# OSO-SWAT-A1-05-BLUE.net
KiCad netlist of a schematic drawn in EAGLE
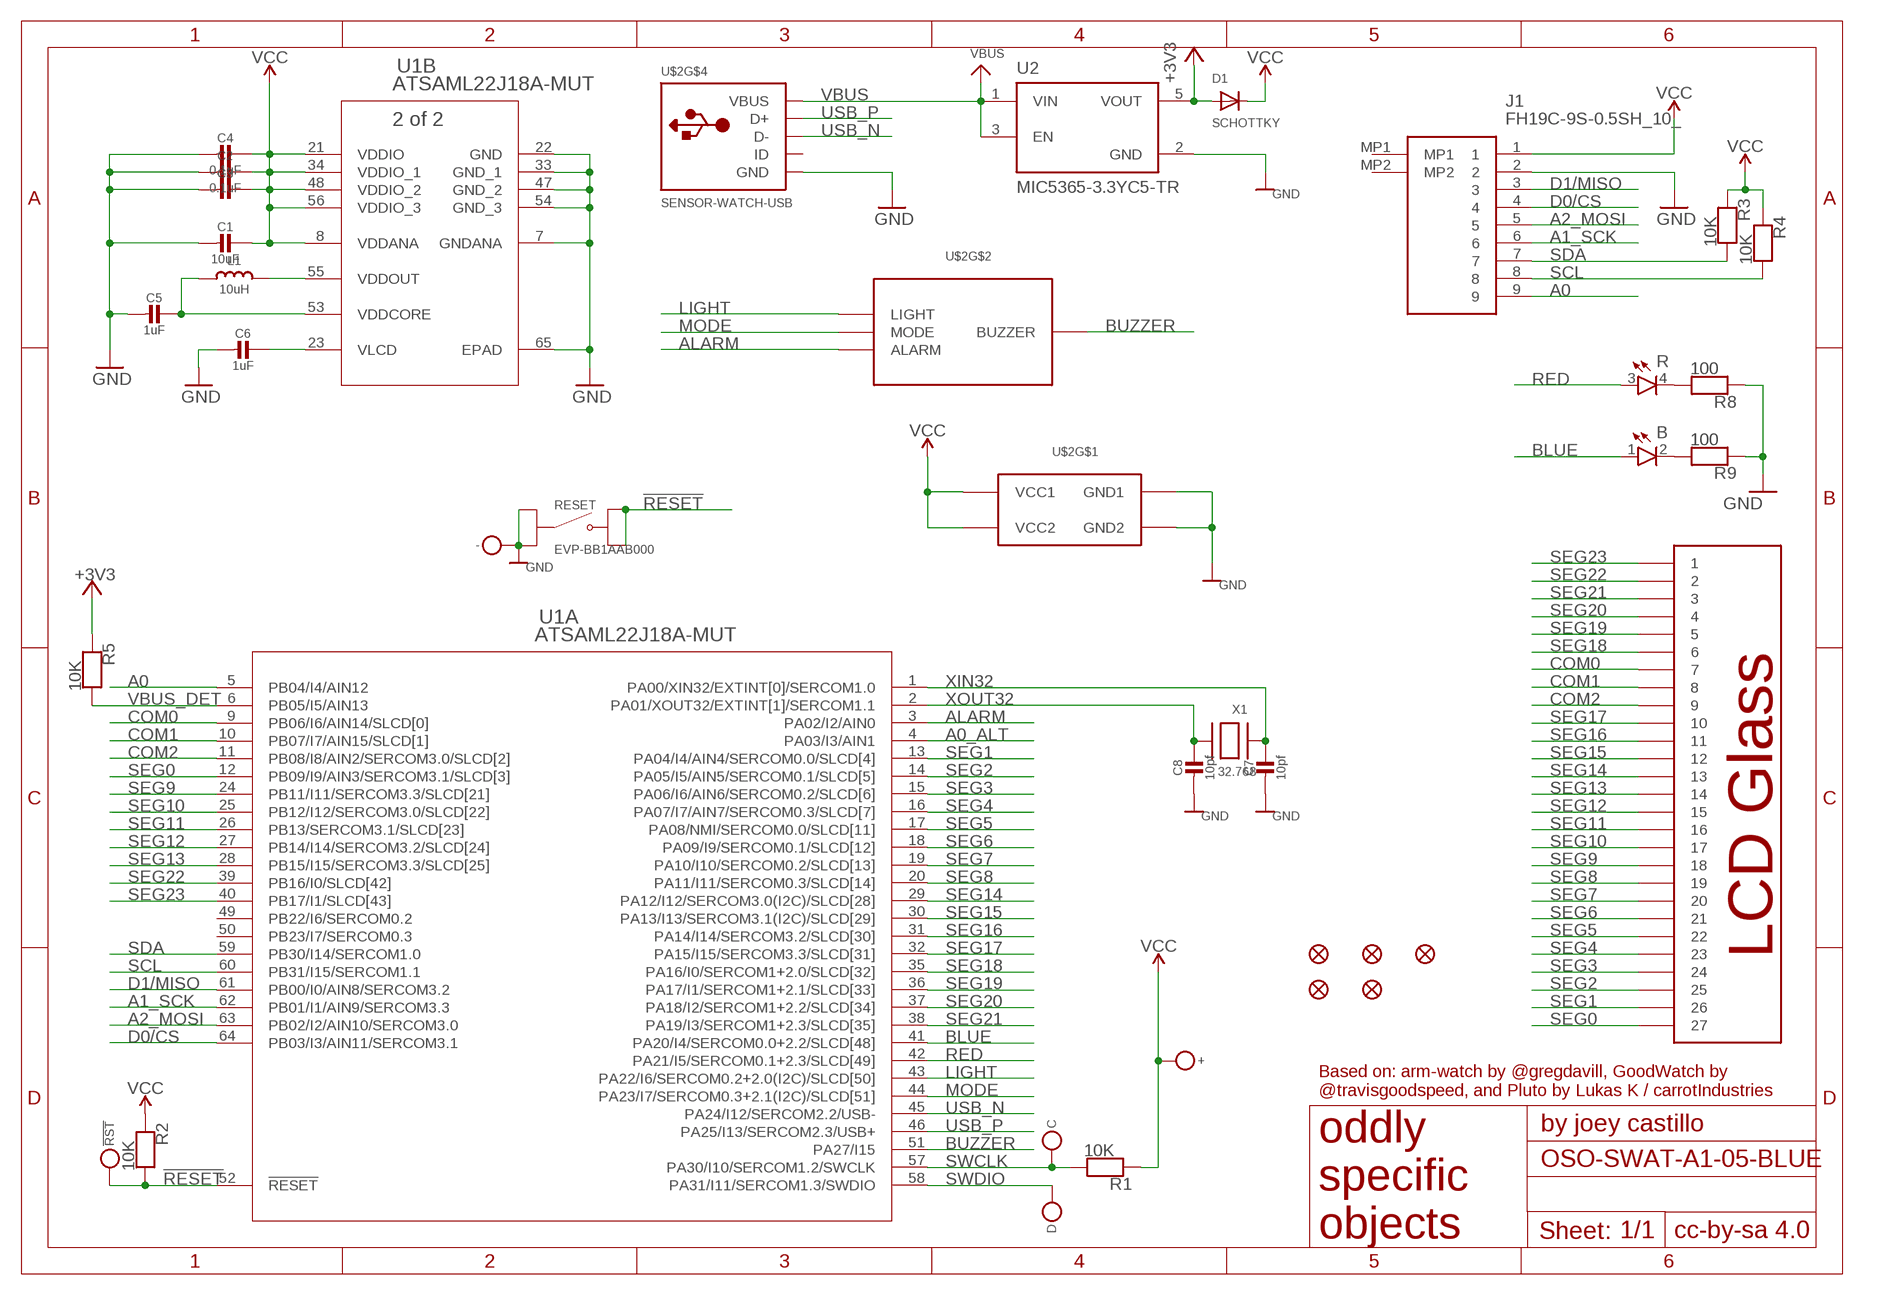
[diagram p0: schematic, sheet 1]

(export (version "E")
  (design (tool "Eeschema 10.0.6"))
  (components
    (comp (ref "!RST")
      (value "MICROBUILDER_TESTPOINTROUND1.5MM")
      (footprint "eagle-import:MICROBUILDER_TESTPOINT_ROUND_1.5MM")
      (libsource (lib "eagle-import") (part "MICROBUILDER_TESTPOINTROUND1.5MM"))
    )
    (comp (ref "+")
      (value "MICROBUILDER_TESTPOINTROUND1.5MM")
      (footprint "eagle-import:MICROBUILDER_TESTPOINT_ROUND_1.5MM")
      (libsource (lib "eagle-import") (part "MICROBUILDER_TESTPOINTROUND1.5MM"))
    )
    (comp (ref "-")
      (value "MICROBUILDER_TESTPOINTROUND1.5MM")
      (footprint "eagle-import:MICROBUILDER_TESTPOINT_ROUND_1.5MM")
      (libsource (lib "eagle-import") (part "MICROBUILDER_TESTPOINTROUND1.5MM"))
    )
    (comp (ref "C")
      (value "MICROBUILDER_TESTPOINTROUND1.5MM")
      (footprint "eagle-import:MICROBUILDER_TESTPOINT_ROUND_1.5MM")
      (libsource (lib "eagle-import") (part "MICROBUILDER_TESTPOINTROUND1.5MM"))
    )
    (comp (ref "C1")
      (value "10uF")
      (footprint "eagle-import:_0603MP")
      (libsource (lib "eagle-import") (part "CAP_CERAMIC_0603MP"))
    )
    (comp (ref "C2")
      (value "0.1uF")
      (footprint "eagle-import:_0603MP")
      (libsource (lib "eagle-import") (part "CAP_CERAMIC_0603MP"))
    )
    (comp (ref "C3")
      (value "0.1uF")
      (footprint "eagle-import:_0603MP")
      (libsource (lib "eagle-import") (part "CAP_CERAMIC_0603MP"))
    )
    (comp (ref "C4")
      (value "0.1uF")
      (footprint "eagle-import:_0603MP")
      (libsource (lib "eagle-import") (part "CAP_CERAMIC_0603MP"))
    )
    (comp (ref "C5")
      (value "1uF")
      (footprint "eagle-import:_0603MP")
      (libsource (lib "eagle-import") (part "CAP_CERAMIC_0603MP"))
    )
    (comp (ref "C6")
      (value "1uF")
      (footprint "eagle-import:_0603MP")
      (libsource (lib "eagle-import") (part "CAP_CERAMIC_0603MP"))
    )
    (comp (ref "C7")
      (value "10pf")
      (footprint "eagle-import:_0402MP")
      (libsource (lib "eagle-import") (part "CAP_CERAMIC_0402MP"))
    )
    (comp (ref "C8")
      (value "10pf")
      (footprint "eagle-import:_0402MP")
      (libsource (lib "eagle-import") (part "CAP_CERAMIC_0402MP"))
    )
    (comp (ref "D")
      (value "MICROBUILDER_TESTPOINTROUND1.5MM")
      (footprint "eagle-import:MICROBUILDER_TESTPOINT_ROUND_1.5MM")
      (libsource (lib "eagle-import") (part "MICROBUILDER_TESTPOINTROUND1.5MM"))
    )
    (comp (ref "D1")
      (value "SCHOTTKY")
      (footprint "eagle-import:SOD-323F")
      (libsource (lib "eagle-import") (part "DIODESOD-323F"))
    )
    (comp (ref "FID1")
      (value "FIDUCIAL_1MM")
      (footprint "eagle-import:FIDUCIAL_1MM")
      (libsource (lib "eagle-import") (part "FIDUCIAL_1MM"))
    )
    (comp (ref "FID2")
      (value "FIDUCIAL_1MM")
      (footprint "eagle-import:FIDUCIAL_1MM")
      (libsource (lib "eagle-import") (part "FIDUCIAL_1MM"))
    )
    (comp (ref "FID3")
      (value "FIDUCIAL_1MM")
      (footprint "eagle-import:FIDUCIAL_1MM")
      (fields (field (name "REV") "A"))
      (libsource (lib "eagle-import") (part "FIDUCIAL_1MM"))
    )
    (comp (ref "FID4")
      (value "FIDUCIAL_1MM")
      (footprint "eagle-import:FIDUCIAL_1MM")
      (libsource (lib "eagle-import") (part "FIDUCIAL_1MM"))
    )
    (comp (ref "FID6")
      (value "FIDUCIAL_1MM")
      (footprint "eagle-import:FIDUCIAL_1MM")
      (fields (field (name "REV") "A"))
      (libsource (lib "eagle-import") (part "FIDUCIAL_1MM"))
    )
    (comp (ref "J1")
      (value "FH19C-9S-0.5SH_10_")
      (footprint "eagle-import:FH19C9S05SH10")
      (fields
        (field (name "MANUFACTURER_PART_NUMBER") "FH19C-9S-0.5SH(10)")
        (field (name "MOUSER_PART_NUMBER") "798-FH19C9S05SH10")
      )
      (libsource (lib "eagle-import") (part "FH19C-9S-0.5SH_10_"))
    )
    (comp (ref "L1")
      (value "10uH")
      (footprint "eagle-import:MICROBUILDER__0805MP")
      (libsource (lib "eagle-import") (part "MICROBUILDER_INDUCTOR_0805MP"))
    )
    (comp (ref "LED")
      (value "QBLP655-RIB")
      (footprint "eagle-import:LED_QBLP655")
      (fields
        (field (name "DIGI-KEY_PART_NUMBER") "160-2026-1-ND")
        (field (name "MF") "Lite-On Inc.")
        (field (name "MP") "LTST-C235KGKRKT")
      )
      (libsource (lib "eagle-import") (part "QBLP655-RIB"))
    )
    (comp (ref "R1")
      (value "10K")
      (footprint "eagle-import:_0603MP")
      (libsource (lib "eagle-import") (part "RESISTOR_0603MP"))
    )
    (comp (ref "R2")
      (value "10K")
      (footprint "eagle-import:_0603MP")
      (libsource (lib "eagle-import") (part "RESISTOR_0603MP"))
    )
    (comp (ref "R3")
      (value "10K")
      (footprint "eagle-import:_0603MP")
      (libsource (lib "eagle-import") (part "RESISTOR_0603MP"))
    )
    (comp (ref "R4")
      (value "10K")
      (footprint "eagle-import:_0603MP")
      (libsource (lib "eagle-import") (part "RESISTOR_0603MP"))
    )
    (comp (ref "R5")
      (value "10K")
      (footprint "eagle-import:_0603MP")
      (libsource (lib "eagle-import") (part "RESISTOR_0603MP"))
    )
    (comp (ref "R8")
      (value "100")
      (footprint "eagle-import:_0603MP")
      (libsource (lib "eagle-import") (part "RESISTOR_0603MP"))
    )
    (comp (ref "R9")
      (value "100")
      (footprint "eagle-import:_0603MP")
      (libsource (lib "eagle-import") (part "RESISTOR_0603MP"))
    )
    (comp (ref "RESET")
      (value "EVP-BB1AAB000")
      (footprint "eagle-import:SW_EVP-BB1AAB000")
      (fields
        (field (name "DIGI-KEY_PART_NUMBER") "P124390CT-ND")
        (field (name "MF") "Panasonic Electronic Components")
      )
      (libsource (lib "eagle-import") (part "EVP-BB1AAB000"))
    )
    (comp (ref "U$2")
      (value "SENSOR-WATCH-USB")
      (footprint "eagle-import:CASIO-F91W-OUTLINE-USB")
      (libsource (lib "eagle-import") (part "SENSOR-WATCH-USB"))
    )
    (comp (ref "U1")
      (value "ATSAML22J18A-MUT")
      (footprint "eagle-import:QFN64_9X9MC_MCH")
      (fields (field (name "COPYRIGHT") "Copyright (C) 2018 Accelerated Designs. All rights reserved"))
      (libsource (lib "eagle-import") (part "ATSAML22J18A-MUT"))
    )
    (comp (ref "U2")
      (value "MIC5365-3.3YC5-TR")
      (footprint "eagle-import:SOT65P210X110-5N")
      (fields (field (name "DIGI-KEY_PART_NUMBER") "576-3193-1-ND") (field (name "MF") "Microchip"))
      (libsource (lib "eagle-import") (part "MIC5365-3.3YC5-TR"))
    )
    (comp (ref "X1")
      (value "32.768")
      (footprint "eagle-import:XTAL3215")
      (libsource (lib "eagle-import") (part "XTAL-3.2X1.5"))
    )
  )
  (nets
    (net (code "1") (name "+3V3") (class "Default")
      (node (ref "D1") (pin "A") (pinfunction "A_A") (pintype "passive"))
      (node (ref "R5") (pin "1") (pinfunction "1_1") (pintype "passive"))
      (node (ref "U2") (pin "5") (pinfunction "VOUT_5") (pintype "output"))
    )
    (net (code "2") (name "/A0") (class "Default")
      (node (ref "J1") (pin "9") (pinfunction "9_9") (pintype "bidirectional"))
      (node (ref "U1") (pin "5") (pinfunction "PB04/I4/AIN12_5") (pintype "bidirectional"))
    )
    (net (code "3") (name "/A0_ALT") (class "Default")
      (node (ref "U1") (pin "4") (pinfunction "PA03/I3/AIN1_4") (pintype "bidirectional"))
    )
    (net (code "4") (name "/A1_SCK") (class "Default")
      (node (ref "J1") (pin "6") (pinfunction "6_6") (pintype "bidirectional"))
      (node (ref "U1") (pin "62") (pinfunction "PB01/I1/AIN9/SERCOM3.3_62") (pintype "bidirectional"))
    )
    (net (code "5") (name "/A2_MOSI") (class "Default")
      (node (ref "J1") (pin "5") (pinfunction "5_5") (pintype "bidirectional"))
      (node (ref "U1") (pin "63") (pinfunction "PB02/I2/AIN10/SERCOM3.0_63") (pintype "bidirectional"))
    )
    (net (code "6") (name "/ALARM") (class "Default")
      (node (ref "U$2") (pin "ALARM") (pinfunction "ALARM_ALARM") (pintype "bidirectional"))
      (node (ref "U1") (pin "3") (pinfunction "PA02/I2/AIN0_3") (pintype "bidirectional"))
    )
    (net (code "7") (name "/BLUE") (class "Default")
      (node (ref "LED") (pin "1") (pinfunction "A_1") (pintype "passive"))
      (node (ref "U1") (pin "41") (pinfunction "PA20/I4/SERCOM0.0+2.2/SLCD[48]_41") (pintype "bidirectional"))
    )
    (net (code "8") (name "/BUZZER") (class "Default")
      (node (ref "U$2") (pin "BUZZER") (pinfunction "BUZZER_BUZZER") (pintype "bidirectional"))
      (node (ref "U1") (pin "51") (pinfunction "PA27/I15_51") (pintype "bidirectional"))
    )
    (net (code "9") (name "/COM0") (class "Default")
      (node (ref "U$2") (pin "7") (pinfunction "7_7") (pintype "input"))
      (node (ref "U1") (pin "9") (pinfunction "PB06/I6/AIN14/SLCD[0]_9") (pintype "bidirectional"))
    )
    (net (code "10") (name "/COM1") (class "Default")
      (node (ref "U$2") (pin "8") (pinfunction "8_8") (pintype "input"))
      (node (ref "U1") (pin "10") (pinfunction "PB07/I7/AIN15/SLCD[1]_10") (pintype "bidirectional"))
    )
    (net (code "11") (name "/COM2") (class "Default")
      (node (ref "U$2") (pin "9") (pinfunction "9_9") (pintype "input"))
      (node (ref "U1") (pin "11") (pinfunction "PB08/I8/AIN2/SERCOM3.0/SLCD[2]_11") (pintype "bidirectional"))
    )
    (net (code "12") (name "/D0{slash}CS") (class "Default")
      (node (ref "J1") (pin "4") (pinfunction "4_4") (pintype "bidirectional"))
      (node (ref "U1") (pin "64") (pinfunction "PB03/I3/AIN11/SERCOM3.1_64") (pintype "bidirectional"))
    )
    (net (code "13") (name "/D1{slash}MISO") (class "Default")
      (node (ref "J1") (pin "3") (pinfunction "3_3") (pintype "bidirectional"))
      (node (ref "U1") (pin "61") (pinfunction "PB00/I0/AIN8/SERCOM3.2_61") (pintype "bidirectional"))
    )
    (net (code "14") (name "/LIGHT") (class "Default")
      (node (ref "U$2") (pin "LIGHT") (pinfunction "LIGHT_LIGHT") (pintype "bidirectional"))
      (node (ref "U1") (pin "43") (pinfunction "PA22/I6/SERCOM0.2+2.0(I2C)/SLCD[50]_43") (pintype "bidirectional"))
    )
    (net (code "15") (name "/MODE") (class "Default")
      (node (ref "U$2") (pin "MODE") (pinfunction "MODE_MODE") (pintype "bidirectional"))
      (node (ref "U1") (pin "44") (pinfunction "PA23/I7/SERCOM0.3+2.1(I2C)/SLCD[51]_44") (pintype "bidirectional"))
    )
    (net (code "16") (name "/RED") (class "Default")
      (node (ref "LED") (pin "3") (pinfunction "A_3") (pintype "passive"))
      (node (ref "U1") (pin "42") (pinfunction "PA21/I5/SERCOM0.1+2.3/SLCD[49]_42") (pintype "bidirectional"))
    )
    (net (code "17") (name "/SCL") (class "Default")
      (node (ref "J1") (pin "8") (pinfunction "8_8") (pintype "bidirectional"))
      (node (ref "R4") (pin "2") (pinfunction "2_2") (pintype "passive"))
      (node (ref "U1") (pin "60") (pinfunction "PB31/I15/SERCOM1.1_60") (pintype "bidirectional"))
    )
    (net (code "18") (name "/SDA") (class "Default")
      (node (ref "J1") (pin "7") (pinfunction "7_7") (pintype "bidirectional"))
      (node (ref "R3") (pin "2") (pinfunction "2_2") (pintype "passive"))
      (node (ref "U1") (pin "59") (pinfunction "PB30/I14/SERCOM1.0_59") (pintype "bidirectional"))
    )
    (net (code "19") (name "/SEG0") (class "Default")
      (node (ref "U$2") (pin "27") (pinfunction "27_27") (pintype "input"))
      (node (ref "U1") (pin "12") (pinfunction "PB09/I9/AIN3/SERCOM3.1/SLCD[3]_12") (pintype "bidirectional"))
    )
    (net (code "20") (name "/SEG1") (class "Default")
      (node (ref "U$2") (pin "26") (pinfunction "26_26") (pintype "input"))
      (node (ref "U1") (pin "13") (pinfunction "PA04/I4/AIN4/SERCOM0.0/SLCD[4]_13") (pintype "bidirectional"))
    )
    (net (code "21") (name "/SEG2") (class "Default")
      (node (ref "U$2") (pin "25") (pinfunction "25_25") (pintype "input"))
      (node (ref "U1") (pin "14") (pinfunction "PA05/I5/AIN5/SERCOM0.1/SLCD[5]_14") (pintype "bidirectional"))
    )
    (net (code "22") (name "/SEG3") (class "Default")
      (node (ref "U$2") (pin "24") (pinfunction "24_24") (pintype "input"))
      (node (ref "U1") (pin "15") (pinfunction "PA06/I6/AIN6/SERCOM0.2/SLCD[6]_15") (pintype "bidirectional"))
    )
    (net (code "23") (name "/SEG4") (class "Default")
      (node (ref "U$2") (pin "23") (pinfunction "23_23") (pintype "input"))
      (node (ref "U1") (pin "16") (pinfunction "PA07/I7/AIN7/SERCOM0.3/SLCD[7]_16") (pintype "bidirectional"))
    )
    (net (code "24") (name "/SEG5") (class "Default")
      (node (ref "U$2") (pin "22") (pinfunction "22_22") (pintype "input"))
      (node (ref "U1") (pin "17") (pinfunction "PA08/NMI/SERCOM0.0/SLCD[11]_17") (pintype "bidirectional"))
    )
    (net (code "25") (name "/SEG6") (class "Default")
      (node (ref "U$2") (pin "21") (pinfunction "21_21") (pintype "input"))
      (node (ref "U1") (pin "18") (pinfunction "PA09/I9/SERCOM0.1/SLCD[12]_18") (pintype "bidirectional"))
    )
    (net (code "26") (name "/SEG7") (class "Default")
      (node (ref "U$2") (pin "20") (pinfunction "20_20") (pintype "input"))
      (node (ref "U1") (pin "19") (pinfunction "PA10/I10/SERCOM0.2/SLCD[13]_19") (pintype "bidirectional"))
    )
    (net (code "27") (name "/SEG8") (class "Default")
      (node (ref "U$2") (pin "19") (pinfunction "19_19") (pintype "input"))
      (node (ref "U1") (pin "20") (pinfunction "PA11/I11/SERCOM0.3/SLCD[14]_20") (pintype "bidirectional"))
    )
    (net (code "28") (name "/SEG9") (class "Default")
      (node (ref "U$2") (pin "18") (pinfunction "18_18") (pintype "input"))
      (node (ref "U1") (pin "24") (pinfunction "PB11/I11/SERCOM3.3/SLCD[21]_24") (pintype "bidirectional"))
    )
    (net (code "29") (name "/SEG10") (class "Default")
      (node (ref "U$2") (pin "17") (pinfunction "17_17") (pintype "input"))
      (node (ref "U1") (pin "25") (pinfunction "PB12/I12/SERCOM3.0/SLCD[22]_25") (pintype "bidirectional"))
    )
    (net (code "30") (name "/SEG11") (class "Default")
      (node (ref "U$2") (pin "16") (pinfunction "16_16") (pintype "input"))
      (node (ref "U1") (pin "26") (pinfunction "PB13/SERCOM3.1/SLCD[23]_26") (pintype "bidirectional"))
    )
    (net (code "31") (name "/SEG12") (class "Default")
      (node (ref "U$2") (pin "15") (pinfunction "15_15") (pintype "input"))
      (node (ref "U1") (pin "27") (pinfunction "PB14/I14/SERCOM3.2/SLCD[24]_27") (pintype "bidirectional"))
    )
    (net (code "32") (name "/SEG13") (class "Default")
      (node (ref "U$2") (pin "14") (pinfunction "14_14") (pintype "input"))
      (node (ref "U1") (pin "28") (pinfunction "PB15/I15/SERCOM3.3/SLCD[25]_28") (pintype "bidirectional"))
    )
    (net (code "33") (name "/SEG14") (class "Default")
      (node (ref "U$2") (pin "13") (pinfunction "13_13") (pintype "input"))
      (node (ref "U1") (pin "29") (pinfunction "PA12/I12/SERCOM3.0(I2C)/SLCD[28]_29") (pintype "bidirectional"))
    )
    (net (code "34") (name "/SEG15") (class "Default")
      (node (ref "U$2") (pin "12") (pinfunction "12_12") (pintype "input"))
      (node (ref "U1") (pin "30") (pinfunction "PA13/I13/SERCOM3.1(I2C)/SLCD[29]_30") (pintype "bidirectional"))
    )
    (net (code "35") (name "/SEG16") (class "Default")
      (node (ref "U$2") (pin "11") (pinfunction "11_11") (pintype "input"))
      (node (ref "U1") (pin "31") (pinfunction "PA14/I14/SERCOM3.2/SLCD[30]_31") (pintype "bidirectional"))
    )
    (net (code "36") (name "/SEG17") (class "Default")
      (node (ref "U$2") (pin "10") (pinfunction "10_10") (pintype "input"))
      (node (ref "U1") (pin "32") (pinfunction "PA15/I15/SERCOM3.3/SLCD[31]_32") (pintype "bidirectional"))
    )
    (net (code "37") (name "/SEG18") (class "Default")
      (node (ref "U$2") (pin "6") (pinfunction "6_6") (pintype "input"))
      (node (ref "U1") (pin "35") (pinfunction "PA16/I0/SERCOM1+2.0/SLCD[32]_35") (pintype "bidirectional"))
    )
    (net (code "38") (name "/SEG19") (class "Default")
      (node (ref "U$2") (pin "5") (pinfunction "5_5") (pintype "input"))
      (node (ref "U1") (pin "36") (pinfunction "PA17/I1/SERCOM1+2.1/SLCD[33]_36") (pintype "bidirectional"))
    )
    (net (code "39") (name "/SEG20") (class "Default")
      (node (ref "U$2") (pin "4") (pinfunction "4_4") (pintype "input"))
      (node (ref "U1") (pin "37") (pinfunction "PA18/I2/SERCOM1+2.2/SLCD[34]_37") (pintype "bidirectional"))
    )
    (net (code "40") (name "/SEG21") (class "Default")
      (node (ref "U$2") (pin "3") (pinfunction "3_3") (pintype "input"))
      (node (ref "U1") (pin "38") (pinfunction "PA19/I3/SERCOM1+2.3/SLCD[35]_38") (pintype "bidirectional"))
    )
    (net (code "41") (name "/SEG22") (class "Default")
      (node (ref "U$2") (pin "2") (pinfunction "2_2") (pintype "input"))
      (node (ref "U1") (pin "39") (pinfunction "PB16/I0/SLCD[42]_39") (pintype "bidirectional"))
    )
    (net (code "42") (name "/SEG23") (class "Default")
      (node (ref "U$2") (pin "1") (pinfunction "1_1") (pintype "input"))
      (node (ref "U1") (pin "40") (pinfunction "PB17/I1/SLCD[43]_40") (pintype "bidirectional"))
    )
    (net (code "43") (name "/SWCLK") (class "Default")
      (node (ref "C") (pin "P$1") (pinfunction "P$1_P$1") (pintype "bidirectional"))
      (node (ref "R1") (pin "2") (pinfunction "2_2") (pintype "passive"))
      (node (ref "U1") (pin "57") (pinfunction "PA30/I10/SERCOM1.2/SWCLK_57") (pintype "bidirectional"))
    )
    (net (code "44") (name "/SWDIO") (class "Default")
      (node (ref "D") (pin "P$1") (pinfunction "P$1_P$1") (pintype "bidirectional"))
      (node (ref "U1") (pin "58") (pinfunction "PA31/I11/SERCOM1.3/SWDIO_58") (pintype "bidirectional"))
    )
    (net (code "45") (name "/USB_N") (class "Default")
      (node (ref "U$2") (pin "USB_N") (pinfunction "D-_USB_N") (pintype "bidirectional"))
      (node (ref "U1") (pin "45") (pinfunction "PA24/I12/SERCOM2.2/USB-_45") (pintype "bidirectional"))
    )
    (net (code "46") (name "/USB_P") (class "Default")
      (node (ref "U$2") (pin "USB_P") (pinfunction "D+_USB_P") (pintype "bidirectional"))
      (node (ref "U1") (pin "46") (pinfunction "PA25/I13/SERCOM2.3/USB+_46") (pintype "bidirectional"))
    )
    (net (code "47") (name "/VBUS_DET") (class "Default")
      (node (ref "R5") (pin "2") (pinfunction "2_2") (pintype "passive"))
      (node (ref "U1") (pin "6") (pinfunction "PB05/I5/AIN13_6") (pintype "bidirectional"))
    )
    (net (code "48") (name "/XIN32") (class "Default")
      (node (ref "C7") (pin "1") (pinfunction "1_1") (pintype "passive"))
      (node (ref "U1") (pin "1") (pinfunction "PA00/XIN32/EXTINT[0]/SERCOM1.0_1") (pintype "bidirectional"))
      (node (ref "X1") (pin "P$1") (pinfunction "P$1_P$1") (pintype "bidirectional"))
    )
    (net (code "49") (name "/XOUT32") (class "Default")
      (node (ref "C8") (pin "1") (pinfunction "1_1") (pintype "passive"))
      (node (ref "U1") (pin "2") (pinfunction "PA01/XOUT32/EXTINT[1]/SERCOM1.1_2") (pintype "bidirectional"))
      (node (ref "X1") (pin "P$2") (pinfunction "P$2_P$2") (pintype "bidirectional"))
    )
    (net (code "50") (name "/~{RESET}") (class "Default")
      (node (ref "!RST") (pin "P$1") (pinfunction "P$1_P$1") (pintype "bidirectional"))
      (node (ref "R2") (pin "2") (pinfunction "2_2") (pintype "passive"))
      (node (ref "RESET") (pin "B1") (pinfunction "B1_B1") (pintype "passive"))
      (node (ref "RESET") (pin "B2") (pinfunction "B2_B2") (pintype "passive"))
      (node (ref "U1") (pin "52") (pinfunction "~{RESET}_52") (pintype "bidirectional"))
    )
    (net (code "51") (name "GND") (class "Default")
      (node (ref "-") (pin "P$1") (pinfunction "P$1_P$1") (pintype "bidirectional"))
      (node (ref "C1") (pin "2") (pinfunction "2_2") (pintype "passive"))
      (node (ref "C2") (pin "2") (pinfunction "2_2") (pintype "passive"))
      (node (ref "C3") (pin "2") (pinfunction "2_2") (pintype "passive"))
      (node (ref "C4") (pin "2") (pinfunction "2_2") (pintype "passive"))
      (node (ref "C5") (pin "2") (pinfunction "2_2") (pintype "passive"))
      (node (ref "C6") (pin "2") (pinfunction "2_2") (pintype "passive"))
      (node (ref "C7") (pin "2") (pinfunction "2_2") (pintype "passive"))
      (node (ref "C8") (pin "2") (pinfunction "2_2") (pintype "passive"))
      (node (ref "J1") (pin "2") (pinfunction "2_2") (pintype "bidirectional"))
      (node (ref "R8") (pin "1") (pinfunction "1_1") (pintype "passive"))
      (node (ref "R9") (pin "1") (pinfunction "1_1") (pintype "passive"))
      (node (ref "RESET") (pin "A1") (pinfunction "A1_A1") (pintype "passive"))
      (node (ref "RESET") (pin "A2") (pinfunction "A2_A2") (pintype "passive"))
      (node (ref "U$2") (pin "GND") (pinfunction "GND_GND") (pintype "power_in"))
      (node (ref "U$2") (pin "GND1") (pinfunction "GND1_GND1") (pintype "bidirectional"))
      (node (ref "U$2") (pin "GND2") (pinfunction "GND2_GND2") (pintype "bidirectional"))
      (node (ref "U1") (pin "22") (pinfunction "GND_22") (pintype "passive"))
      (node (ref "U1") (pin "33") (pinfunction "GND_1_33") (pintype "passive"))
      (node (ref "U1") (pin "47") (pinfunction "GND_2_47") (pintype "passive"))
      (node (ref "U1") (pin "54") (pinfunction "GND_3_54") (pintype "passive"))
      (node (ref "U1") (pin "65") (pinfunction "EPAD_65") (pintype "passive"))
      (node (ref "U1") (pin "7") (pinfunction "GNDANA_7") (pintype "passive"))
      (node (ref "U2") (pin "2") (pinfunction "GND_2") (pintype "power_in"))
    )
    (net (code "52") (name "Net-(LEDA-C)") (class "Default")
      (node (ref "LED") (pin "2") (pinfunction "C_2") (pintype "passive"))
      (node (ref "R9") (pin "2") (pinfunction "2_2") (pintype "passive"))
    )
    (net (code "53") (name "Net-(LEDB-C)") (class "Default")
      (node (ref "LED") (pin "4") (pinfunction "C_4") (pintype "passive"))
      (node (ref "R8") (pin "2") (pinfunction "2_2") (pintype "passive"))
    )
    (net (code "54") (name "Net-(U1B-VDDCORE)") (class "Default")
      (node (ref "C5") (pin "1") (pinfunction "1_1") (pintype "passive"))
      (node (ref "L1") (pin "1") (pinfunction "1_1") (pintype "passive"))
      (node (ref "U1") (pin "53") (pinfunction "VDDCORE_53") (pintype "power_in"))
    )
    (net (code "55") (name "Net-(U1B-VDDOUT)") (class "Default")
      (node (ref "L1") (pin "2") (pinfunction "2_2") (pintype "passive"))
      (node (ref "U1") (pin "55") (pinfunction "VDDOUT_55") (pintype "output"))
    )
    (net (code "56") (name "Net-(U1B-VLCD)") (class "Default")
      (node (ref "C6") (pin "1") (pinfunction "1_1") (pintype "passive"))
      (node (ref "U1") (pin "23") (pinfunction "VLCD_23") (pintype "passive"))
    )
    (net (code "57") (name "VBUS") (class "Default")
      (node (ref "U$2") (pin "VBUS") (pinfunction "VBUS_VBUS") (pintype "power_in"))
      (node (ref "U2") (pin "1") (pinfunction "VIN_1") (pintype "input"))
      (node (ref "U2") (pin "3") (pinfunction "EN_3") (pintype "input"))
    )
    (net (code "58") (name "VCC") (class "Default")
      (node (ref "+") (pin "P$1") (pinfunction "P$1_P$1") (pintype "bidirectional"))
      (node (ref "C1") (pin "1") (pinfunction "1_1") (pintype "passive"))
      (node (ref "C2") (pin "1") (pinfunction "1_1") (pintype "passive"))
      (node (ref "C3") (pin "1") (pinfunction "1_1") (pintype "passive"))
      (node (ref "C4") (pin "1") (pinfunction "1_1") (pintype "passive"))
      (node (ref "D1") (pin "C") (pinfunction "C_C") (pintype "passive"))
      (node (ref "J1") (pin "1") (pinfunction "1_1") (pintype "bidirectional"))
      (node (ref "R1") (pin "1") (pinfunction "1_1") (pintype "passive"))
      (node (ref "R2") (pin "1") (pinfunction "1_1") (pintype "passive"))
      (node (ref "R3") (pin "1") (pinfunction "1_1") (pintype "passive"))
      (node (ref "R4") (pin "1") (pinfunction "1_1") (pintype "passive"))
      (node (ref "U$2") (pin "VCC1") (pinfunction "VCC1_VCC1") (pintype "bidirectional"))
      (node (ref "U$2") (pin "VCC2") (pinfunction "VCC2_VCC2") (pintype "bidirectional"))
      (node (ref "U1") (pin "21") (pinfunction "VDDIO_21") (pintype "power_in"))
      (node (ref "U1") (pin "34") (pinfunction "VDDIO_1_34") (pintype "power_in"))
      (node (ref "U1") (pin "48") (pinfunction "VDDIO_2_48") (pintype "power_in"))
      (node (ref "U1") (pin "56") (pinfunction "VDDIO_3_56") (pintype "power_in"))
      (node (ref "U1") (pin "8") (pinfunction "VDDANA_8") (pintype "power_in"))
    )
    (net (code "59") (name "unconnected-(J1-PadMP1)") (class "Default")
      (node (ref "J1") (pin "MP1") (pinfunction "MP1_MP1") (pintype "bidirectional"))
    )
    (net (code "60") (name "unconnected-(J1-PadMP2)") (class "Default")
      (node (ref "J1") (pin "MP2") (pinfunction "MP2_MP2") (pintype "bidirectional"))
    )
    (net (code "61") (name "unconnected-(U$2D-ID-PadUSB_ID)") (class "Default")
      (node (ref "U$2") (pin "USB_ID") (pinfunction "ID_USB_ID") (pintype "bidirectional"))
    )
    (net (code "62") (name "unconnected-(U1A-PB22{slash}I6{slash}SERCOM0.2-Pad49)") (class "Default")
      (node (ref "U1") (pin "49") (pinfunction "PB22/I6/SERCOM0.2_49") (pintype "bidirectional"))
    )
    (net (code "63") (name "unconnected-(U1A-PB23{slash}I7{slash}SERCOM0.3-Pad50)") (class "Default")
      (node (ref "U1") (pin "50") (pinfunction "PB23/I7/SERCOM0.3_50") (pintype "bidirectional"))
    )
  )
)
